# timing.net
KiCad netlist of a schematic drawn in Altium Designer
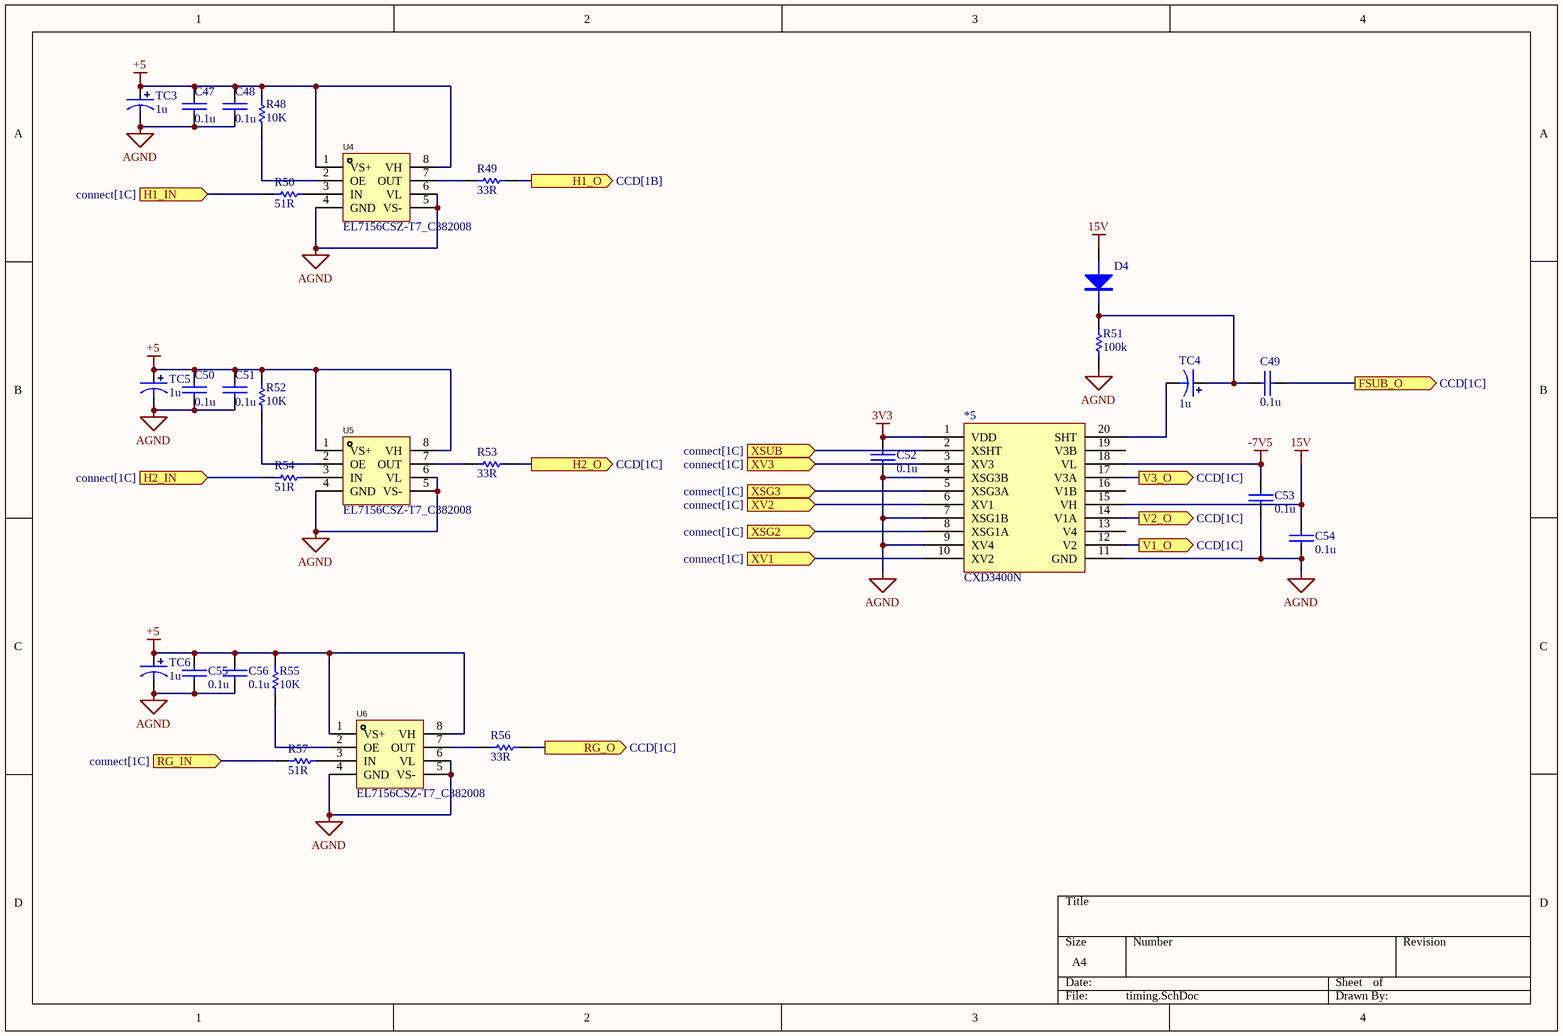
[diagram p0: timing.SchDoc]

(export (version "E")
  (design (tool "Eeschema 10.0.6"))
  (components
    (comp (ref "*5")
      (value "CXD3400N")
      (footprint "CXD3400N")
      (description "6通道垂直时钟驱动器")
      (libsource (lib "0.05-mylib") (part "CXD3400N"))
    )
    (comp (ref "C47")
      (value "0.1u")
      (footprint "0603C")
      (description "无极性电容")
      (libsource (lib "1.00-阻容感") (part "CAP"))
    )
    (comp (ref "C48")
      (value "0.1u")
      (footprint "0603C")
      (description "无极性电容")
      (libsource (lib "1.00-阻容感") (part "CAP"))
    )
    (comp (ref "C49")
      (value "0.1u")
      (footprint "0603C")
      (description "无极性电容")
      (libsource (lib "1.00-阻容感") (part "CAP"))
    )
    (comp (ref "C50")
      (value "0.1u")
      (footprint "0603C")
      (description "无极性电容")
      (libsource (lib "1.00-阻容感") (part "CAP"))
    )
    (comp (ref "C51")
      (value "0.1u")
      (footprint "0603C")
      (description "无极性电容")
      (libsource (lib "1.00-阻容感") (part "CAP"))
    )
    (comp (ref "C52")
      (value "0.1u")
      (footprint "0603C")
      (description "无极性电容")
      (libsource (lib "1.00-阻容感") (part "CAP"))
    )
    (comp (ref "C53")
      (value "0.1u")
      (footprint "0603C")
      (description "无极性电容")
      (libsource (lib "1.00-阻容感") (part "CAP"))
    )
    (comp (ref "C54")
      (value "0.1u")
      (footprint "0603C")
      (description "无极性电容")
      (libsource (lib "1.00-阻容感") (part "CAP"))
    )
    (comp (ref "C55")
      (value "0.1u")
      (footprint "0603C")
      (description "无极性电容")
      (libsource (lib "1.00-阻容感") (part "CAP"))
    )
    (comp (ref "C56")
      (value "0.1u")
      (footprint "0603C")
      (description "无极性电容")
      (libsource (lib "1.00-阻容感") (part "CAP"))
    )
    (comp (ref "D4")
      (value "DIODE")
      (footprint "SOD-123")
      (description "普通二极管")
      (libsource (lib "2.00-二极管") (part "DIODE"))
    )
    (comp (ref "R48")
      (value "10K")
      (footprint "0603R")
      (description "电阻")
      (libsource (lib "1.00-阻容感") (part "RES"))
    )
    (comp (ref "R49")
      (value "33R")
      (footprint "0603R")
      (description "电阻")
      (libsource (lib "1.00-阻容感") (part "RES"))
    )
    (comp (ref "R50")
      (value "51R")
      (footprint "0603R")
      (description "电阻")
      (libsource (lib "1.00-阻容感") (part "RES"))
    )
    (comp (ref "R51")
      (value "100k")
      (footprint "0603R")
      (description "电阻")
      (libsource (lib "1.00-阻容感") (part "RES"))
    )
    (comp (ref "R52")
      (value "10K")
      (footprint "0603R")
      (description "电阻")
      (libsource (lib "1.00-阻容感") (part "RES"))
    )
    (comp (ref "R53")
      (value "33R")
      (footprint "0603R")
      (description "电阻")
      (libsource (lib "1.00-阻容感") (part "RES"))
    )
    (comp (ref "R54")
      (value "51R")
      (footprint "0603R")
      (description "电阻")
      (libsource (lib "1.00-阻容感") (part "RES"))
    )
    (comp (ref "R55")
      (value "10K")
      (footprint "0603R")
      (description "电阻")
      (libsource (lib "1.00-阻容感") (part "RES"))
    )
    (comp (ref "R56")
      (value "33R")
      (footprint "0603R")
      (description "电阻")
      (libsource (lib "1.00-阻容感") (part "RES"))
    )
    (comp (ref "R57")
      (value "51R")
      (footprint "0603R")
      (description "电阻")
      (libsource (lib "1.00-阻容感") (part "RES"))
    )
    (comp (ref "TC3")
      (value "1u")
      (footprint "TAJ-A/3216")
      (description "钽电容")
      (libsource (lib "1.00-阻容感") (part "TCAP"))
    )
    (comp (ref "TC4")
      (value "1u")
      (footprint "TAJ-A/3216")
      (description "钽电容")
      (libsource (lib "1.00-阻容感") (part "TCAP"))
    )
    (comp (ref "TC5")
      (value "1u")
      (footprint "TAJ-A/3216")
      (description "钽电容")
      (libsource (lib "1.00-阻容感") (part "TCAP"))
    )
    (comp (ref "TC6")
      (value "1u")
      (footprint "TAJ-A/3216")
      (description "钽电容")
      (libsource (lib "1.00-阻容感") (part "TCAP"))
    )
    (comp (ref "U4")
      (value "EL7156CSZ-T7_C382008")
      (footprint "SOIC-8")
      (description "栅极驱动器")
      (fields
        (field (name "MANUFACTURER") "Intersil(英特矽尔)")
        (field (name "MANUFACTURER PART") "EL7156CSZ-T7")
      )
      (libsource (lib "0.05-mylib") (part "EL7156CSZ-T7"))
    )
    (comp (ref "U5")
      (value "EL7156CSZ-T7_C382008")
      (footprint "SOIC-8")
      (description "栅极驱动器")
      (fields
        (field (name "MANUFACTURER") "Intersil(英特矽尔)")
        (field (name "MANUFACTURER PART") "EL7156CSZ-T7")
      )
      (libsource (lib "0.05-mylib") (part "EL7156CSZ-T7"))
    )
    (comp (ref "U6")
      (value "EL7156CSZ-T7_C382008")
      (footprint "SOIC-8")
      (description "栅极驱动器")
      (fields
        (field (name "MANUFACTURER") "Intersil(英特矽尔)")
        (field (name "MANUFACTURER PART") "EL7156CSZ-T7")
      )
      (libsource (lib "0.05-mylib") (part "EL7156CSZ-T7"))
    )
  )
  (nets
    (net (code "1") (name "+5") (class "Default")
      (node (ref "C47") (pin "1") (pinfunction "1_1") (pintype "passive"))
      (node (ref "C48") (pin "1") (pinfunction "1_1") (pintype "passive"))
      (node (ref "C50") (pin "1") (pinfunction "1_1") (pintype "passive"))
      (node (ref "C51") (pin "1") (pinfunction "1_1") (pintype "passive"))
      (node (ref "C55") (pin "1") (pinfunction "1_1") (pintype "passive"))
      (node (ref "C56") (pin "1") (pinfunction "1_1") (pintype "passive"))
      (node (ref "R48") (pin "1") (pinfunction "1_1") (pintype "passive"))
      (node (ref "R52") (pin "1") (pinfunction "1_1") (pintype "passive"))
      (node (ref "R55") (pin "1") (pinfunction "1_1") (pintype "passive"))
      (node (ref "TC3") (pin "1") (pinfunction "1_1") (pintype "passive"))
      (node (ref "TC5") (pin "1") (pinfunction "1_1") (pintype "passive"))
      (node (ref "TC6") (pin "1") (pinfunction "1_1") (pintype "passive"))
      (node (ref "U4") (pin "1") (pinfunction "VS+_1") (pintype "passive"))
      (node (ref "U4") (pin "8") (pinfunction "VH_8") (pintype "passive"))
      (node (ref "U5") (pin "1") (pinfunction "VS+_1") (pintype "passive"))
      (node (ref "U5") (pin "8") (pinfunction "VH_8") (pintype "passive"))
      (node (ref "U6") (pin "1") (pinfunction "VS+_1") (pintype "passive"))
      (node (ref "U6") (pin "8") (pinfunction "VH_8") (pintype "passive"))
    )
    (net (code "2") (name "-7V5") (class "Default")
      (node (ref "*5") (pin "18") (pinfunction "VL_18") (pintype "passive"))
      (node (ref "C53") (pin "2") (pinfunction "2_2") (pintype "passive"))
    )
    (net (code "3") (name "/FSUB_O") (class "Default")
      (node (ref "C49") (pin "1") (pinfunction "1_1") (pintype "passive"))
    )
    (net (code "4") (name "/H1_IN") (class "Default")
      (node (ref "R50") (pin "2") (pinfunction "2_2") (pintype "passive"))
    )
    (net (code "5") (name "/H1_O") (class "Default")
      (node (ref "R49") (pin "1") (pinfunction "1_1") (pintype "passive"))
    )
    (net (code "6") (name "/H2_IN") (class "Default")
      (node (ref "R54") (pin "2") (pinfunction "2_2") (pintype "passive"))
    )
    (net (code "7") (name "/H2_O") (class "Default")
      (node (ref "R53") (pin "1") (pinfunction "1_1") (pintype "passive"))
    )
    (net (code "8") (name "/RG_IN") (class "Default")
      (node (ref "R57") (pin "2") (pinfunction "2_2") (pintype "passive"))
    )
    (net (code "9") (name "/RG_O") (class "Default")
      (node (ref "R56") (pin "1") (pinfunction "1_1") (pintype "passive"))
    )
    (net (code "10") (name "/V1_O") (class "Default")
      (node (ref "*5") (pin "12") (pinfunction "V2_12") (pintype "passive"))
    )
    (net (code "11") (name "/V2_O") (class "Default")
      (node (ref "*5") (pin "14") (pinfunction "V1A_14") (pintype "passive"))
    )
    (net (code "12") (name "/V3_O") (class "Default")
      (node (ref "*5") (pin "17") (pinfunction "V3A_17") (pintype "passive"))
    )
    (net (code "13") (name "/XSG2") (class "Default")
      (node (ref "*5") (pin "8") (pinfunction "XSG1A_8") (pintype "passive"))
    )
    (net (code "14") (name "/XSG3") (class "Default")
      (node (ref "*5") (pin "5") (pinfunction "XSG3A_5") (pintype "passive"))
    )
    (net (code "15") (name "/XSUB") (class "Default")
      (node (ref "*5") (pin "2") (pinfunction "XSHT_2") (pintype "passive"))
    )
    (net (code "16") (name "/XV1") (class "Default")
      (node (ref "*5") (pin "10") (pinfunction "XV2_10") (pintype "passive"))
    )
    (net (code "17") (name "/XV2") (class "Default")
      (node (ref "*5") (pin "6") (pinfunction "XV1_6") (pintype "passive"))
    )
    (net (code "18") (name "/XV3") (class "Default")
      (node (ref "*5") (pin "3") (pinfunction "XV3_3") (pintype "passive"))
    )
    (net (code "19") (name "3V3") (class "Default")
      (node (ref "*5") (pin "1") (pinfunction "VDD_1") (pintype "passive"))
      (node (ref "C52") (pin "2") (pinfunction "2_2") (pintype "passive"))
    )
    (net (code "20") (name "15V") (class "Default")
      (node (ref "*5") (pin "15") (pinfunction "VH_15") (pintype "passive"))
      (node (ref "C54") (pin "2") (pinfunction "2_2") (pintype "passive"))
      (node (ref "D4") (pin "A") (pinfunction "A_A") (pintype "passive"))
    )
    (net (code "21") (name "AGND") (class "Default")
      (node (ref "*5") (pin "11") (pinfunction "GND_11") (pintype "passive"))
      (node (ref "*5") (pin "4") (pinfunction "XSG3B_4") (pintype "passive"))
      (node (ref "*5") (pin "7") (pinfunction "XSG1B_7") (pintype "passive"))
      (node (ref "*5") (pin "9") (pinfunction "XV4_9") (pintype "passive"))
      (node (ref "C47") (pin "2") (pinfunction "2_2") (pintype "passive"))
      (node (ref "C48") (pin "2") (pinfunction "2_2") (pintype "passive"))
      (node (ref "C50") (pin "2") (pinfunction "2_2") (pintype "passive"))
      (node (ref "C51") (pin "2") (pinfunction "2_2") (pintype "passive"))
      (node (ref "C52") (pin "1") (pinfunction "1_1") (pintype "passive"))
      (node (ref "C53") (pin "1") (pinfunction "1_1") (pintype "passive"))
      (node (ref "C54") (pin "1") (pinfunction "1_1") (pintype "passive"))
      (node (ref "C55") (pin "2") (pinfunction "2_2") (pintype "passive"))
      (node (ref "C56") (pin "2") (pinfunction "2_2") (pintype "passive"))
      (node (ref "R51") (pin "1") (pinfunction "1_1") (pintype "passive"))
      (node (ref "TC3") (pin "2") (pinfunction "2_2") (pintype "passive"))
      (node (ref "TC5") (pin "2") (pinfunction "2_2") (pintype "passive"))
      (node (ref "TC6") (pin "2") (pinfunction "2_2") (pintype "passive"))
      (node (ref "U4") (pin "4") (pinfunction "GND_4") (pintype "passive"))
      (node (ref "U4") (pin "5") (pinfunction "VS-_5") (pintype "passive"))
      (node (ref "U4") (pin "6") (pinfunction "VL_6") (pintype "passive"))
      (node (ref "U5") (pin "4") (pinfunction "GND_4") (pintype "passive"))
      (node (ref "U5") (pin "5") (pinfunction "VS-_5") (pintype "passive"))
      (node (ref "U5") (pin "6") (pinfunction "VL_6") (pintype "passive"))
      (node (ref "U6") (pin "4") (pinfunction "GND_4") (pintype "passive"))
      (node (ref "U6") (pin "5") (pinfunction "VS-_5") (pintype "passive"))
      (node (ref "U6") (pin "6") (pinfunction "VL_6") (pintype "passive"))
    )
    (net (code "22") (name "Net-(*5-SHT)") (class "Default")
      (node (ref "*5") (pin "20") (pinfunction "SHT_20") (pintype "passive"))
      (node (ref "TC4") (pin "2") (pinfunction "2_2") (pintype "passive"))
    )
    (net (code "23") (name "Net-(C49-Pad2)") (class "Default")
      (node (ref "C49") (pin "2") (pinfunction "2_2") (pintype "passive"))
      (node (ref "D4") (pin "K") (pinfunction "K_K") (pintype "passive"))
      (node (ref "R51") (pin "2") (pinfunction "2_2") (pintype "passive"))
      (node (ref "TC4") (pin "1") (pinfunction "1_1") (pintype "passive"))
    )
    (net (code "24") (name "Net-(U4-IN)") (class "Default")
      (node (ref "R50") (pin "1") (pinfunction "1_1") (pintype "passive"))
      (node (ref "U4") (pin "3") (pinfunction "IN_3") (pintype "passive"))
    )
    (net (code "25") (name "Net-(U4-OE)") (class "Default")
      (node (ref "R48") (pin "2") (pinfunction "2_2") (pintype "passive"))
      (node (ref "U4") (pin "2") (pinfunction "OE_2") (pintype "passive"))
    )
    (net (code "26") (name "Net-(U4-OUT)") (class "Default")
      (node (ref "R49") (pin "2") (pinfunction "2_2") (pintype "passive"))
      (node (ref "U4") (pin "7") (pinfunction "OUT_7") (pintype "passive"))
    )
    (net (code "27") (name "Net-(U5-IN)") (class "Default")
      (node (ref "R54") (pin "1") (pinfunction "1_1") (pintype "passive"))
      (node (ref "U5") (pin "3") (pinfunction "IN_3") (pintype "passive"))
    )
    (net (code "28") (name "Net-(U5-OE)") (class "Default")
      (node (ref "R52") (pin "2") (pinfunction "2_2") (pintype "passive"))
      (node (ref "U5") (pin "2") (pinfunction "OE_2") (pintype "passive"))
    )
    (net (code "29") (name "Net-(U5-OUT)") (class "Default")
      (node (ref "R53") (pin "2") (pinfunction "2_2") (pintype "passive"))
      (node (ref "U5") (pin "7") (pinfunction "OUT_7") (pintype "passive"))
    )
    (net (code "30") (name "Net-(U6-IN)") (class "Default")
      (node (ref "R57") (pin "1") (pinfunction "1_1") (pintype "passive"))
      (node (ref "U6") (pin "3") (pinfunction "IN_3") (pintype "passive"))
    )
    (net (code "31") (name "Net-(U6-OE)") (class "Default")
      (node (ref "R55") (pin "2") (pinfunction "2_2") (pintype "passive"))
      (node (ref "U6") (pin "2") (pinfunction "OE_2") (pintype "passive"))
    )
    (net (code "32") (name "Net-(U6-OUT)") (class "Default")
      (node (ref "R56") (pin "2") (pinfunction "2_2") (pintype "passive"))
      (node (ref "U6") (pin "7") (pinfunction "OUT_7") (pintype "passive"))
    )
    (net (code "33") (name "unconnected-(*5-V1B-Pad16)") (class "Default")
      (node (ref "*5") (pin "16") (pinfunction "V1B_16") (pintype "passive"))
    )
    (net (code "34") (name "unconnected-(*5-V3B-Pad19)") (class "Default")
      (node (ref "*5") (pin "19") (pinfunction "V3B_19") (pintype "passive"))
    )
    (net (code "35") (name "unconnected-(*5-V4-Pad13)") (class "Default")
      (node (ref "*5") (pin "13") (pinfunction "V4_13") (pintype "passive"))
    )
  )
)
